# FPGA_IO.net
KiCad netlist of a schematic drawn in Altium Designer
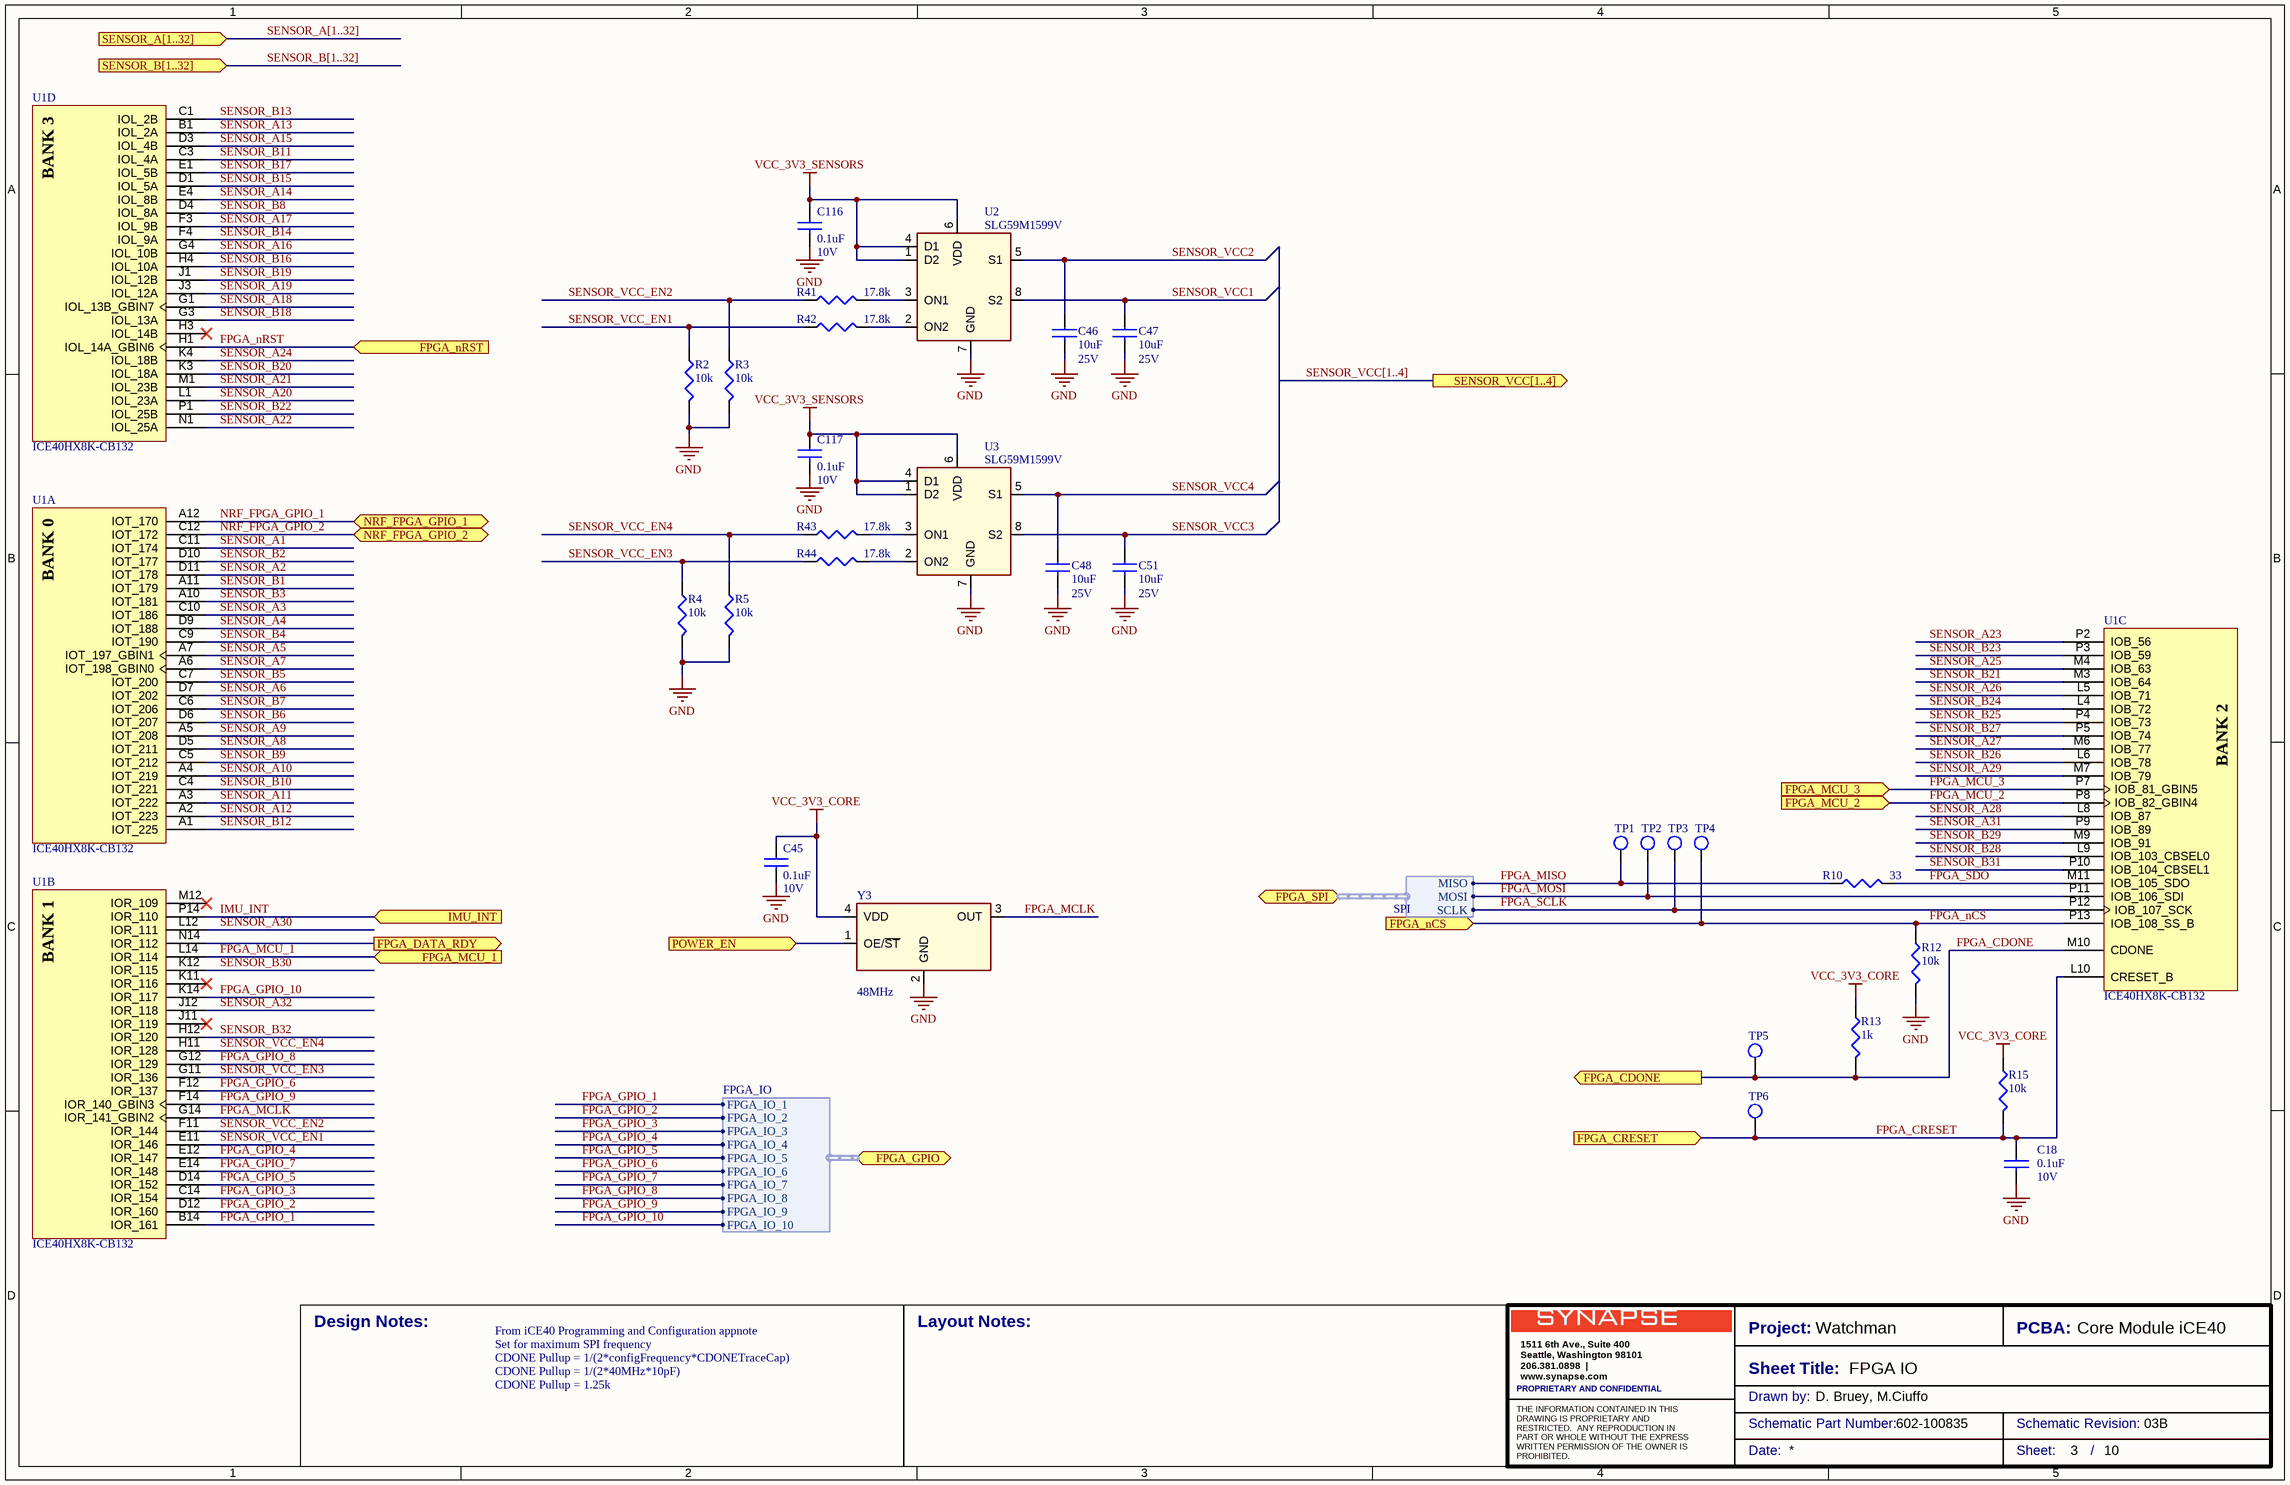
[diagram p0: FPGA_IO.SchDoc]

(export (version "E")
  (design (tool "Eeschema 10.0.6"))
  (components
    (comp (ref "C18")
      (value "0.1uF")
      (footprint "0201-IPCsm_33")
      (description "CAP CER 0.1UF 10V 10% X5R 0201")
      (fields
        (field (name "VOLTAGE") "10V")
        (field (name "MFG") "Samsung Electro-Mechanics America, Inc")
        (field (name "TOLERANCE") "10%")
      )
      (libsource (lib "SynapseLibrary") (part "CAP"))
    )
    (comp (ref "C45")
      (value "0.1uF")
      (footprint "0201-IPCsm_33")
      (description "CAP CER 0.1UF 10V 10% X5R 0201")
      (fields
        (field (name "VOLTAGE") "10V")
        (field (name "MFG") "Samsung Electro-Mechanics America, Inc")
        (field (name "TOLERANCE") "10%")
      )
      (libsource (lib "SynapseLibrary") (part "CAP"))
    )
    (comp (ref "C46")
      (value "10uF")
      (footprint "0603-ipcsm_90")
      (description "CAP CER 10UF 25V 20% X5R 0603")
      (fields
        (field (name "VOLTAGE") "25V")
        (field (name "MFG") "Samsung Electro-Mechanics America, Inc")
        (field (name "TOLERANCE") "20%")
      )
      (libsource (lib "SynapseLibrary") (part "CAP"))
    )
    (comp (ref "C47")
      (value "10uF")
      (footprint "0603-ipcsm_90")
      (description "CAP CER 10UF 25V 20% X5R 0603")
      (fields
        (field (name "VOLTAGE") "25V")
        (field (name "MFG") "Samsung Electro-Mechanics America, Inc")
        (field (name "TOLERANCE") "20%")
      )
      (libsource (lib "SynapseLibrary") (part "CAP"))
    )
    (comp (ref "C48")
      (value "10uF")
      (footprint "0603-ipcsm_90")
      (description "CAP CER 10UF 25V 20% X5R 0603")
      (fields
        (field (name "VOLTAGE") "25V")
        (field (name "MFG") "Samsung Electro-Mechanics America, Inc")
        (field (name "TOLERANCE") "20%")
      )
      (libsource (lib "SynapseLibrary") (part "CAP"))
    )
    (comp (ref "C51")
      (value "10uF")
      (footprint "0603-ipcsm_90")
      (description "CAP CER 10UF 25V 20% X5R 0603")
      (fields
        (field (name "VOLTAGE") "25V")
        (field (name "MFG") "Samsung Electro-Mechanics America, Inc")
        (field (name "TOLERANCE") "20%")
      )
      (libsource (lib "SynapseLibrary") (part "CAP"))
    )
    (comp (ref "C116")
      (value "0.1uF")
      (footprint "0201-IPCsm_33")
      (description "CAP CER 0.1UF 10V 10% X5R 0201")
      (fields
        (field (name "VOLTAGE") "10V")
        (field (name "MFG") "Samsung Electro-Mechanics America, Inc")
        (field (name "TOLERANCE") "10%")
      )
      (libsource (lib "SynapseLibrary") (part "CAP"))
    )
    (comp (ref "C117")
      (value "0.1uF")
      (footprint "0201-IPCsm_33")
      (description "CAP CER 0.1UF 10V 10% X5R 0201")
      (fields
        (field (name "VOLTAGE") "10V")
        (field (name "MFG") "Samsung Electro-Mechanics America, Inc")
        (field (name "TOLERANCE") "10%")
      )
      (libsource (lib "SynapseLibrary") (part "CAP"))
    )
    (comp (ref "R2")
      (value "10k")
      (footprint "0201-IPCsm_26")
      (description "RES 10K OHM 1/20W 1% 0201 SMD")
      (fields (field (name "TOLERANCE") "1.00%") (field (name "VOLTAGE") "50V"))
      (libsource (lib "SynapseLibrary") (part "RES"))
    )
    (comp (ref "R3")
      (value "10k")
      (footprint "0201-IPCsm_26")
      (description "RES 10K OHM 1/20W 1% 0201 SMD")
      (fields (field (name "TOLERANCE") "1.00%") (field (name "VOLTAGE") "50V"))
      (libsource (lib "SynapseLibrary") (part "RES"))
    )
    (comp (ref "R4")
      (value "10k")
      (footprint "0201-IPCsm_26")
      (description "RES 10K OHM 1/20W 1% 0201 SMD")
      (fields (field (name "TOLERANCE") "1.00%") (field (name "VOLTAGE") "50V"))
      (libsource (lib "SynapseLibrary") (part "RES"))
    )
    (comp (ref "R5")
      (value "10k")
      (footprint "0201-IPCsm_26")
      (description "RES 10K OHM 1/20W 1% 0201 SMD")
      (fields (field (name "TOLERANCE") "1.00%") (field (name "VOLTAGE") "50V"))
      (libsource (lib "SynapseLibrary") (part "RES"))
    )
    (comp (ref "R10")
      (value "33")
      (footprint "0201-IPCsm_26")
      (description "RES 33 OHM 1/20W 1% 0201 SMD")
      (fields (field (name "TOLERANCE") "1.00%") (field (name "VOLTAGE") "50V"))
      (libsource (lib "SynapseLibrary") (part "RES"))
    )
    (comp (ref "R12")
      (value "10k")
      (footprint "0201-IPCsm_26")
      (description "RES 10K OHM 1/20W 1% 0201 SMD")
      (fields (field (name "TOLERANCE") "1.00%") (field (name "VOLTAGE") "50V"))
      (libsource (lib "SynapseLibrary") (part "RES"))
    )
    (comp (ref "R13")
      (value "1k")
      (footprint "0201-IPCsm_26")
      (description "RES 1.00K OHM 1/20W 1% 0201 SMD")
      (fields (field (name "TOLERANCE") "1.00%") (field (name "VOLTAGE") "15V"))
      (libsource (lib "SynapseLibrary") (part "RES"))
    )
    (comp (ref "R15")
      (value "10k")
      (footprint "0201-IPCsm_26")
      (description "RES 10K OHM 1/20W 1% 0201 SMD")
      (fields (field (name "TOLERANCE") "1.00%") (field (name "VOLTAGE") "50V"))
      (libsource (lib "SynapseLibrary") (part "RES"))
    )
    (comp (ref "R41")
      (value "17.8k")
      (footprint "0201-IPCsm_26")
      (description "RES SMD 17.8K OHM 1% 1/20W 0201")
      (fields (field (name "TOLERANCE") "1.00%") (field (name "MFG") "PANASONIC"))
      (libsource (lib "SynapseLibrary") (part "RES"))
    )
    (comp (ref "R42")
      (value "17.8k")
      (footprint "0201-IPCsm_26")
      (description "RES SMD 17.8K OHM 1% 1/20W 0201")
      (fields (field (name "TOLERANCE") "1.00%") (field (name "MFG") "PANASONIC"))
      (libsource (lib "SynapseLibrary") (part "RES"))
    )
    (comp (ref "R43")
      (value "17.8k")
      (footprint "0201-IPCsm_26")
      (description "RES SMD 17.8K OHM 1% 1/20W 0201")
      (fields (field (name "TOLERANCE") "1.00%") (field (name "MFG") "PANASONIC"))
      (libsource (lib "SynapseLibrary") (part "RES"))
    )
    (comp (ref "R44")
      (value "17.8k")
      (footprint "0201-IPCsm_26")
      (description "RES SMD 17.8K OHM 1% 1/20W 0201")
      (fields (field (name "TOLERANCE") "1.00%") (field (name "MFG") "PANASONIC"))
      (libsource (lib "SynapseLibrary") (part "RES"))
    )
    (comp (ref "TP1")
      (value "tp-1mm")
      (footprint "TP-S100_SMT")
      (description "TESTPOINT, 1MM SMD, Square pad, Round SM opening")
      (fields (field (name "MFG") "NA"))
      (libsource (lib "SynapseLibrary") (part "tp_smt"))
    )
    (comp (ref "TP2")
      (value "tp-1mm")
      (footprint "TP-S100_SMT")
      (description "TESTPOINT, 1MM SMD, Square pad, Round SM opening")
      (fields (field (name "MFG") "NA"))
      (libsource (lib "SynapseLibrary") (part "tp_smt"))
    )
    (comp (ref "TP3")
      (value "tp-1mm")
      (footprint "TP-S100_SMT")
      (description "TESTPOINT, 1MM SMD, Square pad, Round SM opening")
      (fields (field (name "MFG") "NA"))
      (libsource (lib "SynapseLibrary") (part "tp_smt"))
    )
    (comp (ref "TP4")
      (value "tp-1mm")
      (footprint "TP-S100_SMT")
      (description "TESTPOINT, 1MM SMD, Square pad, Round SM opening")
      (fields (field (name "MFG") "NA"))
      (libsource (lib "SynapseLibrary") (part "tp_smt"))
    )
    (comp (ref "TP5")
      (value "tp-1mm")
      (footprint "TP-S100_SMT")
      (description "TESTPOINT, 1MM SMD, Square pad, Round SM opening")
      (fields (field (name "MFG") "NA"))
      (libsource (lib "SynapseLibrary") (part "tp_smt"))
    )
    (comp (ref "TP6")
      (value "tp-1mm")
      (footprint "TP-S100_SMT")
      (description "TESTPOINT, 1MM SMD, Square pad, Round SM opening")
      (fields (field (name "MFG") "NA"))
      (libsource (lib "SynapseLibrary") (part "tp_smt"))
    )
    (comp (ref "U1")
      (value "ICE40HX8K-CB132")
      (footprint "LATC-csBGA-132")
      (description "IC FPGA 95 I/O 132CBGA")
      (fields (field (name "MFG") "Lattice Semiconductor Corporation") (field (name "VOLTAGE") "1.2-3.3v"))
      (libsource (lib "SynapseLibrary") (part "ICE40HX8K-CB132"))
    )
    (comp (ref "U2")
      (value "SLG59M1599V")
      (footprint "STDFN8_SLG59M1599V")
      (description "Dual 40mohm 1A Load Switch")
      (fields (field (name "MFG") "Silego") (field (name "VOLTAGE") "2.5-5.5V"))
      (libsource (lib "SynapseLibrary") (part "SLG59M1599V"))
    )
    (comp (ref "U3")
      (value "SLG59M1599V")
      (footprint "STDFN8_SLG59M1599V")
      (description "Dual 40mohm 1A Load Switch")
      (fields (field (name "MFG") "Silego") (field (name "VOLTAGE") "2.5-5.5V"))
      (libsource (lib "SynapseLibrary") (part "SLG59M1599V"))
    )
    (comp (ref "Y3")
      (value "48MHz")
      (footprint "XTAL_SiT1602_250x200x80")
      (description "OSC MEMS 48.000MHZ H/LV-CMOS SMD")
      (fields (field (name "MFG") "SiTime") (field (name "VOLTAGE") "3.3V"))
      (libsource (lib "SynapseLibrary") (part "OSC_SiT1602"))
    )
  )
  (nets
    (net (code "3") (name "/FPGA_CDONE") (class "Default")
      (node (ref "R13") (pin "2") (pinfunction "2_2") (pintype "passive"))
      (node (ref "TP5") (pin "1") (pinfunction "TP_1") (pintype "passive"))
      (node (ref "U1") (pin "M10") (pinfunction "CDONE_M10") (pintype "passive"))
    )
    (net (code "4") (name "/FPGA_CRESET") (class "Default")
      (node (ref "C18") (pin "1") (pinfunction "1_1") (pintype "passive"))
      (node (ref "R15") (pin "2") (pinfunction "2_2") (pintype "passive"))
      (node (ref "TP6") (pin "1") (pinfunction "TP_1") (pintype "passive"))
      (node (ref "U1") (pin "L10") (pinfunction "CRESET_B_L10") (pintype "passive"))
    )
    (net (code "5") (name "/FPGA_DATA_RDY") (class "Default")
      (node (ref "U1") (pin "N14") (pinfunction "IOR_112_N14") (pintype "passive"))
    )
    (net (code "6") (name "/FPGA_GPIO_1") (class "Default")
      (node (ref "U1") (pin "B14") (pinfunction "IOR_161_B14") (pintype "passive"))
    )
    (net (code "7") (name "/FPGA_GPIO_2") (class "Default")
      (node (ref "U1") (pin "D12") (pinfunction "IOR_160_D12") (pintype "passive"))
    )
    (net (code "8") (name "/FPGA_GPIO_3") (class "Default")
      (node (ref "U1") (pin "C14") (pinfunction "IOR_154_C14") (pintype "passive"))
    )
    (net (code "9") (name "/FPGA_GPIO_4") (class "Default")
      (node (ref "U1") (pin "E12") (pinfunction "IOR_147_E12") (pintype "passive"))
    )
    (net (code "10") (name "/FPGA_GPIO_5") (class "Default")
      (node (ref "U1") (pin "D14") (pinfunction "IOR_152_D14") (pintype "passive"))
    )
    (net (code "11") (name "/FPGA_GPIO_6") (class "Default")
      (node (ref "U1") (pin "F12") (pinfunction "IOR_137_F12") (pintype "passive"))
    )
    (net (code "12") (name "/FPGA_GPIO_7") (class "Default")
      (node (ref "U1") (pin "E14") (pinfunction "IOR_148_E14") (pintype "passive"))
    )
    (net (code "13") (name "/FPGA_GPIO_8") (class "Default")
      (node (ref "U1") (pin "G12") (pinfunction "IOR_129_G12") (pintype "passive"))
    )
    (net (code "14") (name "/FPGA_GPIO_9") (class "Default")
      (node (ref "U1") (pin "F14") (pinfunction "IOR_140_GBIN3_F14") (pintype "passive"))
    )
    (net (code "15") (name "/FPGA_GPIO_10") (class "Default")
      (node (ref "U1") (pin "K14") (pinfunction "IOR_117_K14") (pintype "passive"))
    )
    (net (code "16") (name "/FPGA_MCLK") (class "Default")
      (node (ref "U1") (pin "G14") (pinfunction "IOR_141_GBIN2_G14") (pintype "passive"))
      (node (ref "Y3") (pin "3") (pinfunction "OUT_3") (pintype "passive"))
    )
    (net (code "17") (name "/FPGA_MCU_1") (class "Default")
      (node (ref "U1") (pin "L14") (pinfunction "IOR_114_L14") (pintype "passive"))
    )
    (net (code "18") (name "/FPGA_MCU_2") (class "Default")
      (node (ref "U1") (pin "P8") (pinfunction "IOB_82_GBIN4_P8") (pintype "passive"))
    )
    (net (code "19") (name "/FPGA_MCU_3") (class "Default")
      (node (ref "U1") (pin "P7") (pinfunction "IOB_81_GBIN5_P7") (pintype "passive"))
    )
    (net (code "20") (name "/FPGA_MISO") (class "Default")
      (node (ref "R10") (pin "1") (pinfunction "1_1") (pintype "passive"))
      (node (ref "TP1") (pin "1") (pinfunction "TP_1") (pintype "passive"))
    )
    (net (code "21") (name "/FPGA_MOSI") (class "Default")
      (node (ref "TP2") (pin "1") (pinfunction "TP_1") (pintype "passive"))
      (node (ref "U1") (pin "P11") (pinfunction "IOB_106_SDI_P11") (pintype "passive"))
    )
    (net (code "22") (name "/FPGA_SCLK") (class "Default")
      (node (ref "TP3") (pin "1") (pinfunction "TP_1") (pintype "passive"))
      (node (ref "U1") (pin "P12") (pinfunction "IOB_107_SCK_P12") (pintype "passive"))
    )
    (net (code "23") (name "/FPGA_SDO") (class "Default")
      (node (ref "R10") (pin "2") (pinfunction "2_2") (pintype "passive"))
      (node (ref "U1") (pin "M11") (pinfunction "IOB_105_SDO_M11") (pintype "passive"))
    )
    (net (code "24") (name "/FPGA_nCS") (class "Default")
      (node (ref "R12") (pin "1") (pinfunction "1_1") (pintype "passive"))
      (node (ref "TP4") (pin "1") (pinfunction "TP_1") (pintype "passive"))
      (node (ref "U1") (pin "P13") (pinfunction "IOB_108_SS_B_P13") (pintype "passive"))
    )
    (net (code "25") (name "/FPGA_nRST") (class "Default")
      (node (ref "U1") (pin "H1") (pinfunction "IOL_14A_GBIN6_H1") (pintype "passive"))
    )
    (net (code "26") (name "/IMU_INT") (class "Default")
      (node (ref "U1") (pin "P14") (pinfunction "IOR_110_P14") (pintype "passive"))
    )
    (net (code "27") (name "/NRF_FPGA_GPIO_1") (class "Default")
      (node (ref "U1") (pin "A12") (pinfunction "IOT_170_A12") (pintype "passive"))
    )
    (net (code "28") (name "/NRF_FPGA_GPIO_2") (class "Default")
      (node (ref "U1") (pin "C12") (pinfunction "IOT_172_C12") (pintype "passive"))
    )
    (net (code "29") (name "/POWER_EN") (class "Default")
      (node (ref "Y3") (pin "1") (pinfunction "OE/~{ST}_1") (pintype "passive"))
    )
    (net (code "30") (name "/SENSOR_A1") (class "Default")
      (node (ref "U1") (pin "C11") (pinfunction "IOT_174_C11") (pintype "passive"))
    )
    (net (code "31") (name "/SENSOR_A2") (class "Default")
      (node (ref "U1") (pin "D11") (pinfunction "IOT_178_D11") (pintype "passive"))
    )
    (net (code "32") (name "/SENSOR_A3") (class "Default")
      (node (ref "U1") (pin "C10") (pinfunction "IOT_186_C10") (pintype "passive"))
    )
    (net (code "33") (name "/SENSOR_A4") (class "Default")
      (node (ref "U1") (pin "D9") (pinfunction "IOT_188_D9") (pintype "passive"))
    )
    (net (code "34") (name "/SENSOR_A5") (class "Default")
      (node (ref "U1") (pin "A7") (pinfunction "IOT_197_GBIN1_A7") (pintype "passive"))
    )
    (net (code "35") (name "/SENSOR_A6") (class "Default")
      (node (ref "U1") (pin "D7") (pinfunction "IOT_202_D7") (pintype "passive"))
    )
    (net (code "36") (name "/SENSOR_A7") (class "Default")
      (node (ref "U1") (pin "A6") (pinfunction "IOT_198_GBIN0_A6") (pintype "passive"))
    )
    (net (code "37") (name "/SENSOR_A8") (class "Default")
      (node (ref "U1") (pin "D5") (pinfunction "IOT_211_D5") (pintype "passive"))
    )
    (net (code "38") (name "/SENSOR_A9") (class "Default")
      (node (ref "U1") (pin "A5") (pinfunction "IOT_208_A5") (pintype "passive"))
    )
    (net (code "39") (name "/SENSOR_A10") (class "Default")
      (node (ref "U1") (pin "A4") (pinfunction "IOT_219_A4") (pintype "passive"))
    )
    (net (code "40") (name "/SENSOR_A11") (class "Default")
      (node (ref "U1") (pin "A3") (pinfunction "IOT_222_A3") (pintype "passive"))
    )
    (net (code "41") (name "/SENSOR_A12") (class "Default")
      (node (ref "U1") (pin "A2") (pinfunction "IOT_223_A2") (pintype "passive"))
    )
    (net (code "42") (name "/SENSOR_A13") (class "Default")
      (node (ref "U1") (pin "B1") (pinfunction "IOL_2A_B1") (pintype "passive"))
    )
    (net (code "43") (name "/SENSOR_A14") (class "Default")
      (node (ref "U1") (pin "E4") (pinfunction "IOL_8B_E4") (pintype "passive"))
    )
    (net (code "44") (name "/SENSOR_A15") (class "Default")
      (node (ref "U1") (pin "D3") (pinfunction "IOL_4B_D3") (pintype "passive"))
    )
    (net (code "45") (name "/SENSOR_A16") (class "Default")
      (node (ref "U1") (pin "G4") (pinfunction "IOL_10B_G4") (pintype "passive"))
    )
    (net (code "46") (name "/SENSOR_A17") (class "Default")
      (node (ref "U1") (pin "F3") (pinfunction "IOL_9B_F3") (pintype "passive"))
    )
    (net (code "47") (name "/SENSOR_A18") (class "Default")
      (node (ref "U1") (pin "G1") (pinfunction "IOL_13B_GBIN7_G1") (pintype "passive"))
    )
    (net (code "48") (name "/SENSOR_A19") (class "Default")
      (node (ref "U1") (pin "J3") (pinfunction "IOL_12A_J3") (pintype "passive"))
    )
    (net (code "49") (name "/SENSOR_A20") (class "Default")
      (node (ref "U1") (pin "L1") (pinfunction "IOL_23A_L1") (pintype "passive"))
    )
    (net (code "50") (name "/SENSOR_A21") (class "Default")
      (node (ref "U1") (pin "M1") (pinfunction "IOL_23B_M1") (pintype "passive"))
    )
    (net (code "51") (name "/SENSOR_A22") (class "Default")
      (node (ref "U1") (pin "N1") (pinfunction "IOL_25A_N1") (pintype "passive"))
    )
    (net (code "52") (name "/SENSOR_A23") (class "Default")
      (node (ref "U1") (pin "P2") (pinfunction "IOB_56_P2") (pintype "passive"))
    )
    (net (code "53") (name "/SENSOR_A24") (class "Default")
      (node (ref "U1") (pin "K4") (pinfunction "IOL_18B_K4") (pintype "passive"))
    )
    (net (code "54") (name "/SENSOR_A25") (class "Default")
      (node (ref "U1") (pin "M4") (pinfunction "IOB_63_M4") (pintype "passive"))
    )
    (net (code "55") (name "/SENSOR_A26") (class "Default")
      (node (ref "U1") (pin "L5") (pinfunction "IOB_71_L5") (pintype "passive"))
    )
    (net (code "56") (name "/SENSOR_A27") (class "Default")
      (node (ref "U1") (pin "M6") (pinfunction "IOB_77_M6") (pintype "passive"))
    )
    (net (code "57") (name "/SENSOR_A28") (class "Default")
      (node (ref "U1") (pin "L8") (pinfunction "IOB_87_L8") (pintype "passive"))
    )
    (net (code "58") (name "/SENSOR_A29") (class "Default")
      (node (ref "U1") (pin "M7") (pinfunction "IOB_79_M7") (pintype "passive"))
    )
    (net (code "59") (name "/SENSOR_A30") (class "Default")
      (node (ref "U1") (pin "L12") (pinfunction "IOR_111_L12") (pintype "passive"))
    )
    (net (code "60") (name "/SENSOR_A31") (class "Default")
      (node (ref "U1") (pin "P9") (pinfunction "IOB_89_P9") (pintype "passive"))
    )
    (net (code "61") (name "/SENSOR_A32") (class "Default")
      (node (ref "U1") (pin "J12") (pinfunction "IOR_118_J12") (pintype "passive"))
    )
    (net (code "63") (name "/SENSOR_B1") (class "Default")
      (node (ref "U1") (pin "A11") (pinfunction "IOT_179_A11") (pintype "passive"))
    )
    (net (code "64") (name "/SENSOR_B2") (class "Default")
      (node (ref "U1") (pin "D10") (pinfunction "IOT_177_D10") (pintype "passive"))
    )
    (net (code "65") (name "/SENSOR_B3") (class "Default")
      (node (ref "U1") (pin "A10") (pinfunction "IOT_181_A10") (pintype "passive"))
    )
    (net (code "66") (name "/SENSOR_B4") (class "Default")
      (node (ref "U1") (pin "C9") (pinfunction "IOT_190_C9") (pintype "passive"))
    )
    (net (code "67") (name "/SENSOR_B5") (class "Default")
      (node (ref "U1") (pin "C7") (pinfunction "IOT_200_C7") (pintype "passive"))
    )
    (net (code "68") (name "/SENSOR_B6") (class "Default")
      (node (ref "U1") (pin "D6") (pinfunction "IOT_207_D6") (pintype "passive"))
    )
    (net (code "69") (name "/SENSOR_B7") (class "Default")
      (node (ref "U1") (pin "C6") (pinfunction "IOT_206_C6") (pintype "passive"))
    )
    (net (code "70") (name "/SENSOR_B8") (class "Default")
      (node (ref "U1") (pin "D4") (pinfunction "IOL_8A_D4") (pintype "passive"))
    )
    (net (code "71") (name "/SENSOR_B9") (class "Default")
      (node (ref "U1") (pin "C5") (pinfunction "IOT_212_C5") (pintype "passive"))
    )
    (net (code "72") (name "/SENSOR_B10") (class "Default")
      (node (ref "U1") (pin "C4") (pinfunction "IOT_221_C4") (pintype "passive"))
    )
    (net (code "73") (name "/SENSOR_B11") (class "Default")
      (node (ref "U1") (pin "C3") (pinfunction "IOL_4A_C3") (pintype "passive"))
    )
    (net (code "74") (name "/SENSOR_B12") (class "Default")
      (node (ref "U1") (pin "A1") (pinfunction "IOT_225_A1") (pintype "passive"))
    )
    (net (code "75") (name "/SENSOR_B13") (class "Default")
      (node (ref "U1") (pin "C1") (pinfunction "IOL_2B_C1") (pintype "passive"))
    )
    (net (code "76") (name "/SENSOR_B14") (class "Default")
      (node (ref "U1") (pin "F4") (pinfunction "IOL_9A_F4") (pintype "passive"))
    )
    (net (code "77") (name "/SENSOR_B15") (class "Default")
      (node (ref "U1") (pin "D1") (pinfunction "IOL_5A_D1") (pintype "passive"))
    )
    (net (code "78") (name "/SENSOR_B16") (class "Default")
      (node (ref "U1") (pin "H4") (pinfunction "IOL_10A_H4") (pintype "passive"))
    )
    (net (code "79") (name "/SENSOR_B17") (class "Default")
      (node (ref "U1") (pin "E1") (pinfunction "IOL_5B_E1") (pintype "passive"))
    )
    (net (code "80") (name "/SENSOR_B18") (class "Default")
      (node (ref "U1") (pin "G3") (pinfunction "IOL_13A_G3") (pintype "passive"))
    )
    (net (code "81") (name "/SENSOR_B19") (class "Default")
      (node (ref "U1") (pin "J1") (pinfunction "IOL_12B_J1") (pintype "passive"))
    )
    (net (code "82") (name "/SENSOR_B20") (class "Default")
      (node (ref "U1") (pin "K3") (pinfunction "IOL_18A_K3") (pintype "passive"))
    )
    (net (code "83") (name "/SENSOR_B21") (class "Default")
      (node (ref "U1") (pin "M3") (pinfunction "IOB_64_M3") (pintype "passive"))
    )
    (net (code "84") (name "/SENSOR_B22") (class "Default")
      (node (ref "U1") (pin "P1") (pinfunction "IOL_25B_P1") (pintype "passive"))
    )
    (net (code "85") (name "/SENSOR_B23") (class "Default")
      (node (ref "U1") (pin "P3") (pinfunction "IOB_59_P3") (pintype "passive"))
    )
    (net (code "86") (name "/SENSOR_B24") (class "Default")
      (node (ref "U1") (pin "L4") (pinfunction "IOB_72_L4") (pintype "passive"))
    )
    (net (code "87") (name "/SENSOR_B25") (class "Default")
      (node (ref "U1") (pin "P4") (pinfunction "IOB_73_P4") (pintype "passive"))
    )
    (net (code "88") (name "/SENSOR_B26") (class "Default")
      (node (ref "U1") (pin "L6") (pinfunction "IOB_78_L6") (pintype "passive"))
    )
    (net (code "89") (name "/SENSOR_B27") (class "Default")
      (node (ref "U1") (pin "P5") (pinfunction "IOB_74_P5") (pintype "passive"))
    )
    (net (code "90") (name "/SENSOR_B28") (class "Default")
      (node (ref "U1") (pin "L9") (pinfunction "IOB_103_CBSEL0_L9") (pintype "passive"))
    )
    (net (code "91") (name "/SENSOR_B29") (class "Default")
      (node (ref "U1") (pin "M9") (pinfunction "IOB_91_M9") (pintype "passive"))
    )
    (net (code "92") (name "/SENSOR_B30") (class "Default")
      (node (ref "U1") (pin "K12") (pinfunction "IOR_115_K12") (pintype "passive"))
    )
    (net (code "93") (name "/SENSOR_B31") (class "Default")
      (node (ref "U1") (pin "P10") (pinfunction "IOB_104_CBSEL1_P10") (pintype "passive"))
    )
    (net (code "94") (name "/SENSOR_B32") (class "Default")
      (node (ref "U1") (pin "H12") (pinfunction "IOR_120_H12") (pintype "passive"))
    )
    (net (code "96") (name "/SENSOR_VCC1") (class "Default")
      (node (ref "C47") (pin "1") (pinfunction "1_1") (pintype "passive"))
      (node (ref "U2") (pin "8") (pinfunction "S2_8") (pintype "passive"))
    )
    (net (code "97") (name "/SENSOR_VCC2") (class "Default")
      (node (ref "C46") (pin "1") (pinfunction "1_1") (pintype "passive"))
      (node (ref "U2") (pin "5") (pinfunction "S1_5") (pintype "passive"))
    )
    (net (code "98") (name "/SENSOR_VCC3") (class "Default")
      (node (ref "C51") (pin "1") (pinfunction "1_1") (pintype "passive"))
      (node (ref "U3") (pin "8") (pinfunction "S2_8") (pintype "passive"))
    )
    (net (code "99") (name "/SENSOR_VCC4") (class "Default")
      (node (ref "C48") (pin "1") (pinfunction "1_1") (pintype "passive"))
      (node (ref "U3") (pin "5") (pinfunction "S1_5") (pintype "passive"))
    )
    (net (code "101") (name "/SENSOR_VCC_EN1") (class "Default")
      (node (ref "R2") (pin "1") (pinfunction "1_1") (pintype "passive"))
      (node (ref "R42") (pin "1") (pinfunction "1_1") (pintype "passive"))
      (node (ref "U1") (pin "E11") (pinfunction "IOR_146_E11") (pintype "passive"))
    )
    (net (code "102") (name "/SENSOR_VCC_EN2") (class "Default")
      (node (ref "R3") (pin "1") (pinfunction "1_1") (pintype "passive"))
      (node (ref "R41") (pin "1") (pinfunction "1_1") (pintype "passive"))
      (node (ref "U1") (pin "F11") (pinfunction "IOR_144_F11") (pintype "passive"))
    )
    (net (code "103") (name "/SENSOR_VCC_EN3") (class "Default")
      (node (ref "R4") (pin "1") (pinfunction "1_1") (pintype "passive"))
      (node (ref "R44") (pin "1") (pinfunction "1_1") (pintype "passive"))
      (node (ref "U1") (pin "G11") (pinfunction "IOR_136_G11") (pintype "passive"))
    )
    (net (code "104") (name "/SENSOR_VCC_EN4") (class "Default")
      (node (ref "R43") (pin "1") (pinfunction "1_1") (pintype "passive"))
      (node (ref "R5") (pin "1") (pinfunction "1_1") (pintype "passive"))
      (node (ref "U1") (pin "H11") (pinfunction "IOR_128_H11") (pintype "passive"))
    )
    (net (code "107") (name "GND") (class "Default")
      (node (ref "C116") (pin "2") (pinfunction "2_2") (pintype "passive"))
      (node (ref "C117") (pin "2") (pinfunction "2_2") (pintype "passive"))
      (node (ref "C18") (pin "2") (pinfunction "2_2") (pintype "passive"))
      (node (ref "C45") (pin "2") (pinfunction "2_2") (pintype "passive"))
      (node (ref "C46") (pin "2") (pinfunction "2_2") (pintype "passive"))
      (node (ref "C47") (pin "2") (pinfunction "2_2") (pintype "passive"))
      (node (ref "C48") (pin "2") (pinfunction "2_2") (pintype "passive"))
      (node (ref "C51") (pin "2") (pinfunction "2_2") (pintype "passive"))
      (node (ref "R12") (pin "2") (pinfunction "2_2") (pintype "passive"))
      (node (ref "R2") (pin "2") (pinfunction "2_2") (pintype "passive"))
      (node (ref "R3") (pin "2") (pinfunction "2_2") (pintype "passive"))
      (node (ref "R4") (pin "2") (pinfunction "2_2") (pintype "passive"))
      (node (ref "R5") (pin "2") (pinfunction "2_2") (pintype "passive"))
      (node (ref "U2") (pin "7") (pinfunction "GND_7") (pintype "passive"))
      (node (ref "U3") (pin "7") (pinfunction "GND_7") (pintype "passive"))
      (node (ref "Y3") (pin "2") (pinfunction "GND_2") (pintype "passive"))
    )
    (net (code "108") (name "Net-(U2-ON1)") (class "Default")
      (node (ref "R41") (pin "2") (pinfunction "2_2") (pintype "passive"))
      (node (ref "U2") (pin "3") (pinfunction "ON1_3") (pintype "passive"))
    )
    (net (code "109") (name "Net-(U2-ON2)") (class "Default")
      (node (ref "R42") (pin "2") (pinfunction "2_2") (pintype "passive"))
      (node (ref "U2") (pin "2") (pinfunction "ON2_2") (pintype "passive"))
    )
    (net (code "110") (name "Net-(U3-ON1)") (class "Default")
      (node (ref "R43") (pin "2") (pinfunction "2_2") (pintype "passive"))
      (node (ref "U3") (pin "3") (pinfunction "ON1_3") (pintype "passive"))
    )
    (net (code "111") (name "Net-(U3-ON2)") (class "Default")
      (node (ref "R44") (pin "2") (pinfunction "2_2") (pintype "passive"))
      (node (ref "U3") (pin "2") (pinfunction "ON2_2") (pintype "passive"))
    )
    (net (code "112") (name "VCC_3V3_CORE") (class "Default")
      (node (ref "C45") (pin "1") (pinfunction "1_1") (pintype "passive"))
      (node (ref "R13") (pin "1") (pinfunction "1_1") (pintype "passive"))
      (node (ref "R15") (pin "1") (pinfunction "1_1") (pintype "passive"))
      (node (ref "Y3") (pin "4") (pinfunction "VDD_4") (pintype "passive"))
    )
    (net (code "113") (name "VCC_3V3_SENSORS") (class "Default")
      (node (ref "C116") (pin "1") (pinfunction "1_1") (pintype "passive"))
      (node (ref "C117") (pin "1") (pinfunction "1_1") (pintype "passive"))
      (node (ref "U2") (pin "1") (pinfunction "D2_1") (pintype "passive"))
      (node (ref "U2") (pin "4") (pinfunction "D1_4") (pintype "passive"))
      (node (ref "U2") (pin "6") (pinfunction "VDD_6") (pintype "passive"))
      (node (ref "U3") (pin "1") (pinfunction "D2_1") (pintype "passive"))
      (node (ref "U3") (pin "4") (pinfunction "D1_4") (pintype "passive"))
      (node (ref "U3") (pin "6") (pinfunction "VDD_6") (pintype "passive"))
    )
    (net (code "114") (name "unconnected-(U1B-IOR_109-PadM12)") (class "Default")
      (node (ref "U1") (pin "M12") (pinfunction "IOR_109_M12") (pintype "passive+no_connect"))
    )
    (net (code "115") (name "unconnected-(U1B-IOR_116-PadK11)") (class "Default")
      (node (ref "U1") (pin "K11") (pinfunction "IOR_116_K11") (pintype "passive+no_connect"))
    )
    (net (code "116") (name "unconnected-(U1B-IOR_119-PadJ11)") (class "Default")
      (node (ref "U1") (pin "J11") (pinfunction "IOR_119_J11") (pintype "passive+no_connect"))
    )
    (net (code "117") (name "unconnected-(U1D-IOL_14B-PadH3)") (class "Default")
      (node (ref "U1") (pin "H3") (pinfunction "IOL_14B_H3") (pintype "passive+no_connect"))
    )
  )
)
